# W026X.net
KiCad netlist of a schematic drawn in EAGLE
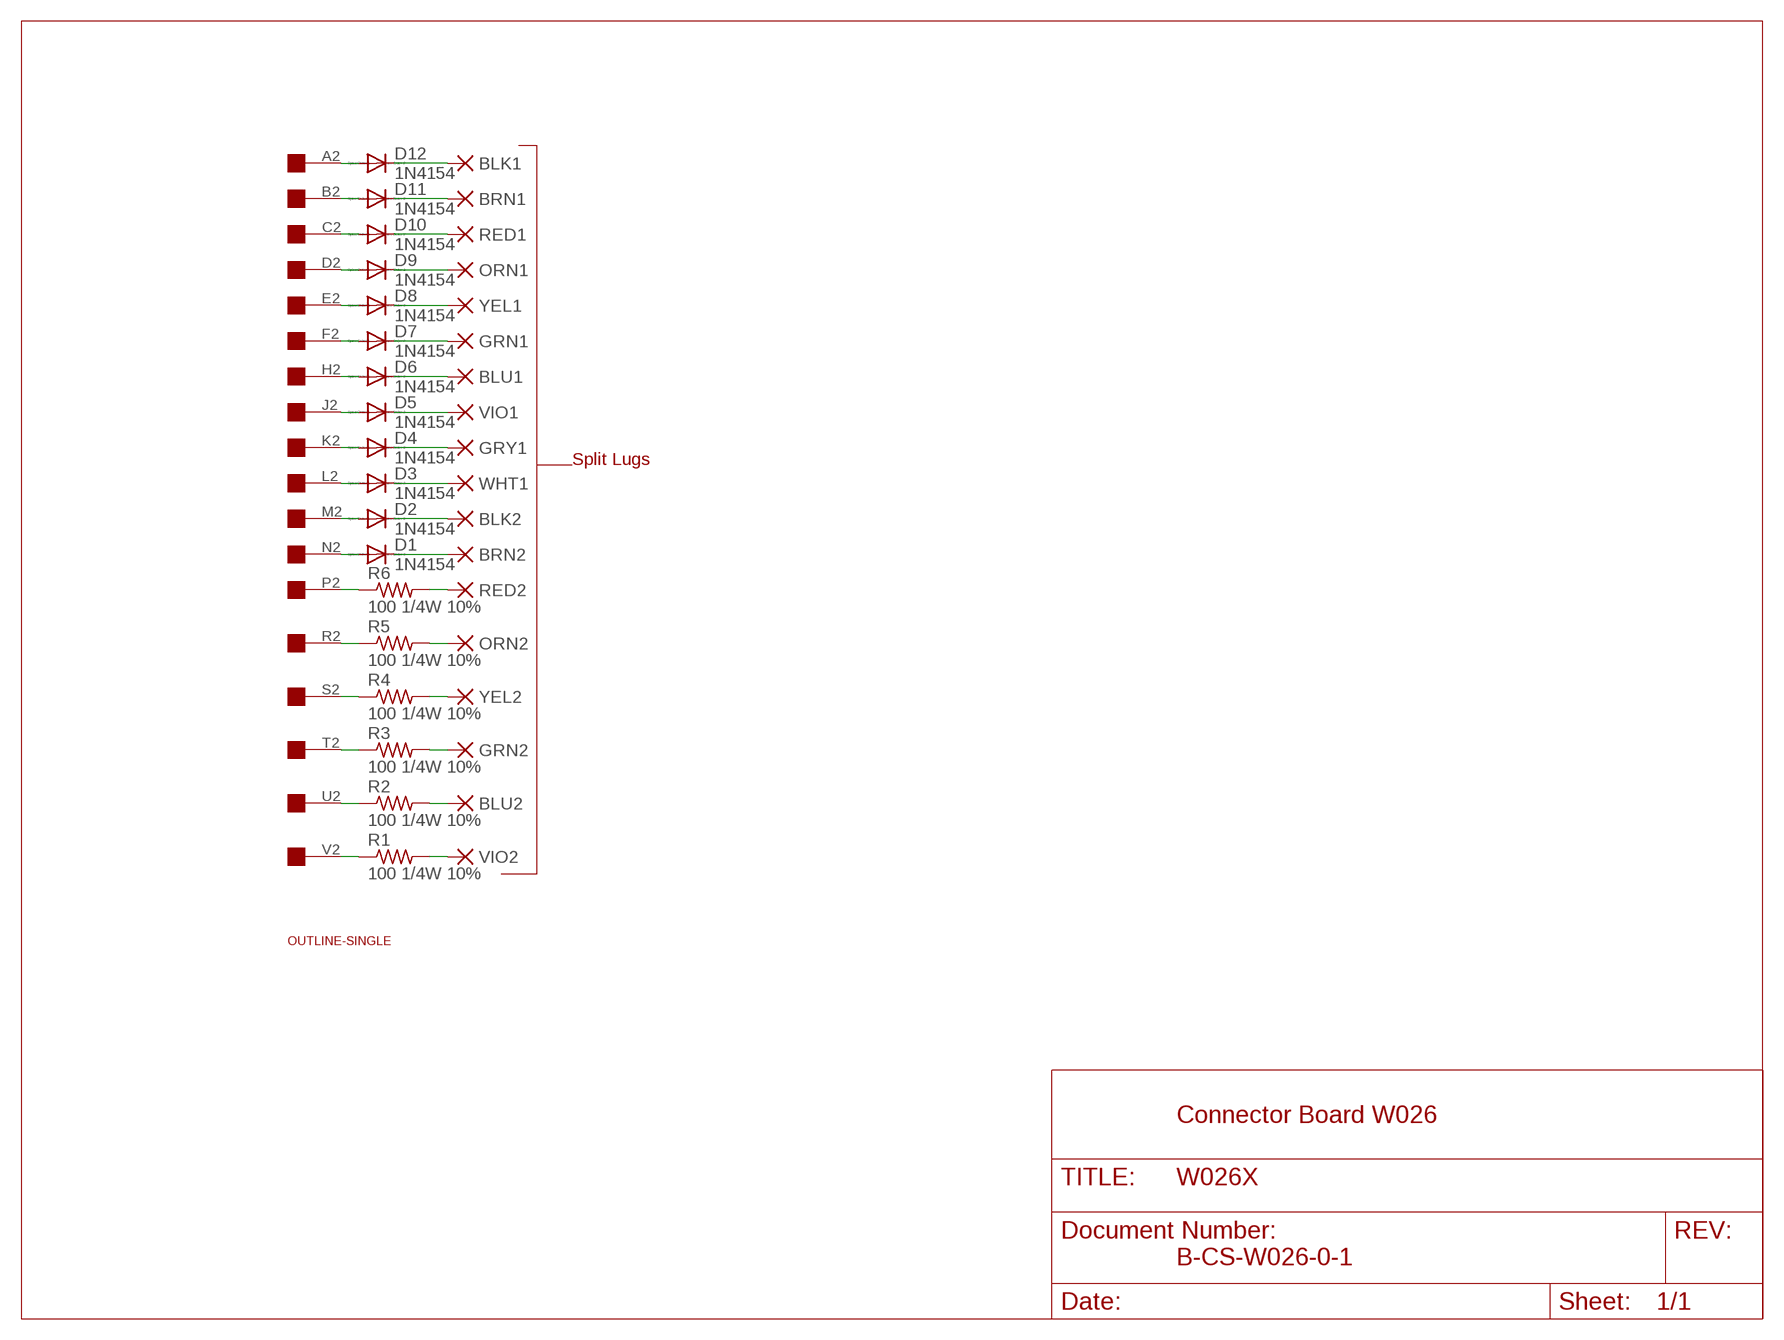
[diagram p0: schematic, sheet 1]

(export (version "E")
  (design (tool "Eeschema 10.0.6"))
  (components
    (comp (ref "BLK1")
      (value "PAD-0465")
      (footprint "eagle-import:0465")
      (libsource (lib "eagle-import") (part "PAD-0465"))
    )
    (comp (ref "BLK2")
      (value "PAD-0465")
      (footprint "eagle-import:0465")
      (libsource (lib "eagle-import") (part "PAD-0465"))
    )
    (comp (ref "BLU1")
      (value "PAD-0465")
      (footprint "eagle-import:0465")
      (libsource (lib "eagle-import") (part "PAD-0465"))
    )
    (comp (ref "BLU2")
      (value "PAD-0465")
      (footprint "eagle-import:0465")
      (libsource (lib "eagle-import") (part "PAD-0465"))
    )
    (comp (ref "BRN1")
      (value "PAD-0465")
      (footprint "eagle-import:0465")
      (libsource (lib "eagle-import") (part "PAD-0465"))
    )
    (comp (ref "BRN2")
      (value "PAD-0465")
      (footprint "eagle-import:0465")
      (libsource (lib "eagle-import") (part "PAD-0465"))
    )
    (comp (ref "D1")
      (value "1N4154")
      (footprint "eagle-import:DO35-10")
      (libsource (lib "eagle-import") (part "1N4148DO35-10"))
    )
    (comp (ref "D2")
      (value "1N4154")
      (footprint "eagle-import:DO35-10")
      (libsource (lib "eagle-import") (part "1N4148DO35-10"))
    )
    (comp (ref "D3")
      (value "1N4154")
      (footprint "eagle-import:DO35-10")
      (libsource (lib "eagle-import") (part "1N4148DO35-10"))
    )
    (comp (ref "D4")
      (value "1N4154")
      (footprint "eagle-import:DO35-10")
      (libsource (lib "eagle-import") (part "1N4148DO35-10"))
    )
    (comp (ref "D5")
      (value "1N4154")
      (footprint "eagle-import:DO35-10")
      (libsource (lib "eagle-import") (part "1N4148DO35-10"))
    )
    (comp (ref "D6")
      (value "1N4154")
      (footprint "eagle-import:DO35-10")
      (libsource (lib "eagle-import") (part "1N4148DO35-10"))
    )
    (comp (ref "D7")
      (value "1N4154")
      (footprint "eagle-import:DO35-10")
      (libsource (lib "eagle-import") (part "1N4148DO35-10"))
    )
    (comp (ref "D8")
      (value "1N4154")
      (footprint "eagle-import:DO35-10")
      (libsource (lib "eagle-import") (part "1N4148DO35-10"))
    )
    (comp (ref "D9")
      (value "1N4154")
      (footprint "eagle-import:DO35-10")
      (libsource (lib "eagle-import") (part "1N4148DO35-10"))
    )
    (comp (ref "D10")
      (value "1N4154")
      (footprint "eagle-import:DO35-10")
      (libsource (lib "eagle-import") (part "1N4148DO35-10"))
    )
    (comp (ref "D11")
      (value "1N4154")
      (footprint "eagle-import:DO35-10")
      (libsource (lib "eagle-import") (part "1N4148DO35-10"))
    )
    (comp (ref "D12")
      (value "1N4154")
      (footprint "eagle-import:DO35-10")
      (libsource (lib "eagle-import") (part "1N4148DO35-10"))
    )
    (comp (ref "GRN1")
      (value "PAD-0465")
      (footprint "eagle-import:0465")
      (libsource (lib "eagle-import") (part "PAD-0465"))
    )
    (comp (ref "GRN2")
      (value "PAD-0465")
      (footprint "eagle-import:0465")
      (libsource (lib "eagle-import") (part "PAD-0465"))
    )
    (comp (ref "GRY1")
      (value "PAD-0465")
      (footprint "eagle-import:0465")
      (libsource (lib "eagle-import") (part "PAD-0465"))
    )
    (comp (ref "ORN1")
      (value "PAD-0465")
      (footprint "eagle-import:0465")
      (libsource (lib "eagle-import") (part "PAD-0465"))
    )
    (comp (ref "ORN2")
      (value "PAD-0465")
      (footprint "eagle-import:0465")
      (libsource (lib "eagle-import") (part "PAD-0465"))
    )
    (comp (ref "R1")
      (value "100 1/4W 10%")
      (footprint "eagle-import:0207_10")
      (libsource (lib "eagle-import") (part "R-US_0207/10"))
    )
    (comp (ref "R2")
      (value "100 1/4W 10%")
      (footprint "eagle-import:0207_10")
      (libsource (lib "eagle-import") (part "R-US_0207/10"))
    )
    (comp (ref "R3")
      (value "100 1/4W 10%")
      (footprint "eagle-import:0207_10")
      (libsource (lib "eagle-import") (part "R-US_0207/10"))
    )
    (comp (ref "R4")
      (value "100 1/4W 10%")
      (footprint "eagle-import:0207_10")
      (libsource (lib "eagle-import") (part "R-US_0207/10"))
    )
    (comp (ref "R5")
      (value "100 1/4W 10%")
      (footprint "eagle-import:0207_10")
      (libsource (lib "eagle-import") (part "R-US_0207/10"))
    )
    (comp (ref "R6")
      (value "100 1/4W 10%")
      (footprint "eagle-import:0207_10")
      (libsource (lib "eagle-import") (part "R-US_0207/10"))
    )
    (comp (ref "RED1")
      (value "PAD-0465")
      (footprint "eagle-import:0465")
      (libsource (lib "eagle-import") (part "PAD-0465"))
    )
    (comp (ref "RED2")
      (value "PAD-0465")
      (footprint "eagle-import:0465")
      (libsource (lib "eagle-import") (part "PAD-0465"))
    )
    (comp (ref "U$1")
      (value "OUTLINE-SINGLE")
      (footprint "eagle-import:SINGLE")
      (libsource (lib "eagle-import") (part "OUTLINE-SINGLE"))
    )
    (comp (ref "U$2")
      (value "EDGE-1")
      (footprint "eagle-import:EDGE-CON1")
      (libsource (lib "eagle-import") (part "EDGE-1"))
    )
    (comp (ref "VIO1")
      (value "PAD-0465")
      (footprint "eagle-import:0465")
      (libsource (lib "eagle-import") (part "PAD-0465"))
    )
    (comp (ref "VIO2")
      (value "PAD-0465")
      (footprint "eagle-import:0465")
      (libsource (lib "eagle-import") (part "PAD-0465"))
    )
    (comp (ref "WHT1")
      (value "PAD-0465")
      (footprint "eagle-import:0465")
      (libsource (lib "eagle-import") (part "PAD-0465"))
    )
    (comp (ref "YEL1")
      (value "PAD-0465")
      (footprint "eagle-import:0465")
      (libsource (lib "eagle-import") (part "PAD-0465"))
    )
    (comp (ref "YEL2")
      (value "PAD-0465")
      (footprint "eagle-import:0465")
      (libsource (lib "eagle-import") (part "PAD-0465"))
    )
  )
  (nets
    (net (code "1") (name "Net-(BLK1-P)") (class "Default")
      (node (ref "BLK1") (pin "P$1") (pinfunction "P_P$1") (pintype "passive"))
      (node (ref "D12") (pin "C") (pinfunction "C_C") (pintype "passive"))
    )
    (net (code "2") (name "Net-(BLK2-P)") (class "Default")
      (node (ref "BLK2") (pin "P$1") (pinfunction "P_P$1") (pintype "passive"))
      (node (ref "D2") (pin "C") (pinfunction "C_C") (pintype "passive"))
    )
    (net (code "3") (name "Net-(BLU1-P)") (class "Default")
      (node (ref "BLU1") (pin "P$1") (pinfunction "P_P$1") (pintype "passive"))
      (node (ref "D6") (pin "C") (pinfunction "C_C") (pintype "passive"))
    )
    (net (code "4") (name "Net-(BLU2-P)") (class "Default")
      (node (ref "BLU2") (pin "P$1") (pinfunction "P_P$1") (pintype "passive"))
      (node (ref "R2") (pin "2") (pinfunction "2_2") (pintype "passive"))
    )
    (net (code "5") (name "Net-(BRN1-P)") (class "Default")
      (node (ref "BRN1") (pin "P$1") (pinfunction "P_P$1") (pintype "passive"))
      (node (ref "D11") (pin "C") (pinfunction "C_C") (pintype "passive"))
    )
    (net (code "6") (name "Net-(BRN2-P)") (class "Default")
      (node (ref "BRN2") (pin "P$1") (pinfunction "P_P$1") (pintype "passive"))
      (node (ref "D1") (pin "C") (pinfunction "C_C") (pintype "passive"))
    )
    (net (code "7") (name "Net-(GRN1-P)") (class "Default")
      (node (ref "D7") (pin "C") (pinfunction "C_C") (pintype "passive"))
      (node (ref "GRN1") (pin "P$1") (pinfunction "P_P$1") (pintype "passive"))
    )
    (net (code "8") (name "Net-(GRN2-P)") (class "Default")
      (node (ref "GRN2") (pin "P$1") (pinfunction "P_P$1") (pintype "passive"))
      (node (ref "R3") (pin "2") (pinfunction "2_2") (pintype "passive"))
    )
    (net (code "9") (name "Net-(GRY1-P)") (class "Default")
      (node (ref "D4") (pin "C") (pinfunction "C_C") (pintype "passive"))
      (node (ref "GRY1") (pin "P$1") (pinfunction "P_P$1") (pintype "passive"))
    )
    (net (code "10") (name "Net-(ORN1-P)") (class "Default")
      (node (ref "D9") (pin "C") (pinfunction "C_C") (pintype "passive"))
      (node (ref "ORN1") (pin "P$1") (pinfunction "P_P$1") (pintype "passive"))
    )
    (net (code "11") (name "Net-(ORN2-P)") (class "Default")
      (node (ref "ORN2") (pin "P$1") (pinfunction "P_P$1") (pintype "passive"))
      (node (ref "R5") (pin "2") (pinfunction "2_2") (pintype "passive"))
    )
    (net (code "12") (name "Net-(RED1-P)") (class "Default")
      (node (ref "D10") (pin "C") (pinfunction "C_C") (pintype "passive"))
      (node (ref "RED1") (pin "P$1") (pinfunction "P_P$1") (pintype "passive"))
    )
    (net (code "13") (name "Net-(RED2-P)") (class "Default")
      (node (ref "R6") (pin "2") (pinfunction "2_2") (pintype "passive"))
      (node (ref "RED2") (pin "P$1") (pinfunction "P_P$1") (pintype "passive"))
    )
    (net (code "14") (name "Net-(U$2A-1)") (class "Default")
      (node (ref "D12") (pin "A") (pinfunction "A_A") (pintype "passive"))
      (node (ref "U$2") (pin "A2") (pinfunction "1_A2") (pintype "bidirectional"))
    )
    (net (code "15") (name "Net-(U$2B-1)") (class "Default")
      (node (ref "D11") (pin "A") (pinfunction "A_A") (pintype "passive"))
      (node (ref "U$2") (pin "B2") (pinfunction "1_B2") (pintype "bidirectional"))
    )
    (net (code "16") (name "Net-(U$2C-1)") (class "Default")
      (node (ref "D10") (pin "A") (pinfunction "A_A") (pintype "passive"))
      (node (ref "U$2") (pin "C2") (pinfunction "1_C2") (pintype "bidirectional"))
    )
    (net (code "17") (name "Net-(U$2D-1)") (class "Default")
      (node (ref "D9") (pin "A") (pinfunction "A_A") (pintype "passive"))
      (node (ref "U$2") (pin "D2") (pinfunction "1_D2") (pintype "bidirectional"))
    )
    (net (code "18") (name "Net-(U$2E-1)") (class "Default")
      (node (ref "D8") (pin "A") (pinfunction "A_A") (pintype "passive"))
      (node (ref "U$2") (pin "E2") (pinfunction "1_E2") (pintype "bidirectional"))
    )
    (net (code "19") (name "Net-(U$2F-1)") (class "Default")
      (node (ref "D7") (pin "A") (pinfunction "A_A") (pintype "passive"))
      (node (ref "U$2") (pin "F2") (pinfunction "1_F2") (pintype "bidirectional"))
    )
    (net (code "20") (name "Net-(U$2G-1)") (class "Default")
      (node (ref "D6") (pin "A") (pinfunction "A_A") (pintype "passive"))
      (node (ref "U$2") (pin "H2") (pinfunction "1_H2") (pintype "bidirectional"))
    )
    (net (code "21") (name "Net-(U$2H-1)") (class "Default")
      (node (ref "D5") (pin "A") (pinfunction "A_A") (pintype "passive"))
      (node (ref "U$2") (pin "J2") (pinfunction "1_J2") (pintype "bidirectional"))
    )
    (net (code "22") (name "Net-(U$2I-1)") (class "Default")
      (node (ref "D4") (pin "A") (pinfunction "A_A") (pintype "passive"))
      (node (ref "U$2") (pin "K2") (pinfunction "1_K2") (pintype "bidirectional"))
    )
    (net (code "23") (name "Net-(U$2J-1)") (class "Default")
      (node (ref "D3") (pin "A") (pinfunction "A_A") (pintype "passive"))
      (node (ref "U$2") (pin "L2") (pinfunction "1_L2") (pintype "bidirectional"))
    )
    (net (code "24") (name "Net-(U$2K-1)") (class "Default")
      (node (ref "D2") (pin "A") (pinfunction "A_A") (pintype "passive"))
      (node (ref "U$2") (pin "M2") (pinfunction "1_M2") (pintype "bidirectional"))
    )
    (net (code "25") (name "Net-(U$2L-1)") (class "Default")
      (node (ref "D1") (pin "A") (pinfunction "A_A") (pintype "passive"))
      (node (ref "U$2") (pin "N2") (pinfunction "1_N2") (pintype "bidirectional"))
    )
    (net (code "26") (name "Net-(U$2M-1)") (class "Default")
      (node (ref "R6") (pin "1") (pinfunction "1_1") (pintype "passive"))
      (node (ref "U$2") (pin "P2") (pinfunction "1_P2") (pintype "bidirectional"))
    )
    (net (code "27") (name "Net-(U$2N-1)") (class "Default")
      (node (ref "R5") (pin "1") (pinfunction "1_1") (pintype "passive"))
      (node (ref "U$2") (pin "R2") (pinfunction "1_R2") (pintype "bidirectional"))
    )
    (net (code "28") (name "Net-(U$2O-1)") (class "Default")
      (node (ref "R4") (pin "1") (pinfunction "1_1") (pintype "passive"))
      (node (ref "U$2") (pin "S2") (pinfunction "1_S2") (pintype "bidirectional"))
    )
    (net (code "29") (name "Net-(U$2P-1)") (class "Default")
      (node (ref "R3") (pin "1") (pinfunction "1_1") (pintype "passive"))
      (node (ref "U$2") (pin "T2") (pinfunction "1_T2") (pintype "bidirectional"))
    )
    (net (code "30") (name "Net-(U$2Q-1)") (class "Default")
      (node (ref "R2") (pin "1") (pinfunction "1_1") (pintype "passive"))
      (node (ref "U$2") (pin "U2") (pinfunction "1_U2") (pintype "bidirectional"))
    )
    (net (code "31") (name "Net-(U$2R-1)") (class "Default")
      (node (ref "R1") (pin "1") (pinfunction "1_1") (pintype "passive"))
      (node (ref "U$2") (pin "V2") (pinfunction "1_V2") (pintype "bidirectional"))
    )
    (net (code "32") (name "Net-(VIO1-P)") (class "Default")
      (node (ref "D5") (pin "C") (pinfunction "C_C") (pintype "passive"))
      (node (ref "VIO1") (pin "P$1") (pinfunction "P_P$1") (pintype "passive"))
    )
    (net (code "33") (name "Net-(VIO2-P)") (class "Default")
      (node (ref "R1") (pin "2") (pinfunction "2_2") (pintype "passive"))
      (node (ref "VIO2") (pin "P$1") (pinfunction "P_P$1") (pintype "passive"))
    )
    (net (code "34") (name "Net-(WHT1-P)") (class "Default")
      (node (ref "D3") (pin "C") (pinfunction "C_C") (pintype "passive"))
      (node (ref "WHT1") (pin "P$1") (pinfunction "P_P$1") (pintype "passive"))
    )
    (net (code "35") (name "Net-(YEL1-P)") (class "Default")
      (node (ref "D8") (pin "C") (pinfunction "C_C") (pintype "passive"))
      (node (ref "YEL1") (pin "P$1") (pinfunction "P_P$1") (pintype "passive"))
    )
    (net (code "36") (name "Net-(YEL2-P)") (class "Default")
      (node (ref "R4") (pin "2") (pinfunction "2_2") (pintype "passive"))
      (node (ref "YEL2") (pin "P$1") (pinfunction "P_P$1") (pintype "passive"))
    )
  )
)
